# RevE-light.net
KiCad netlist of a schematic drawn in EAGLE
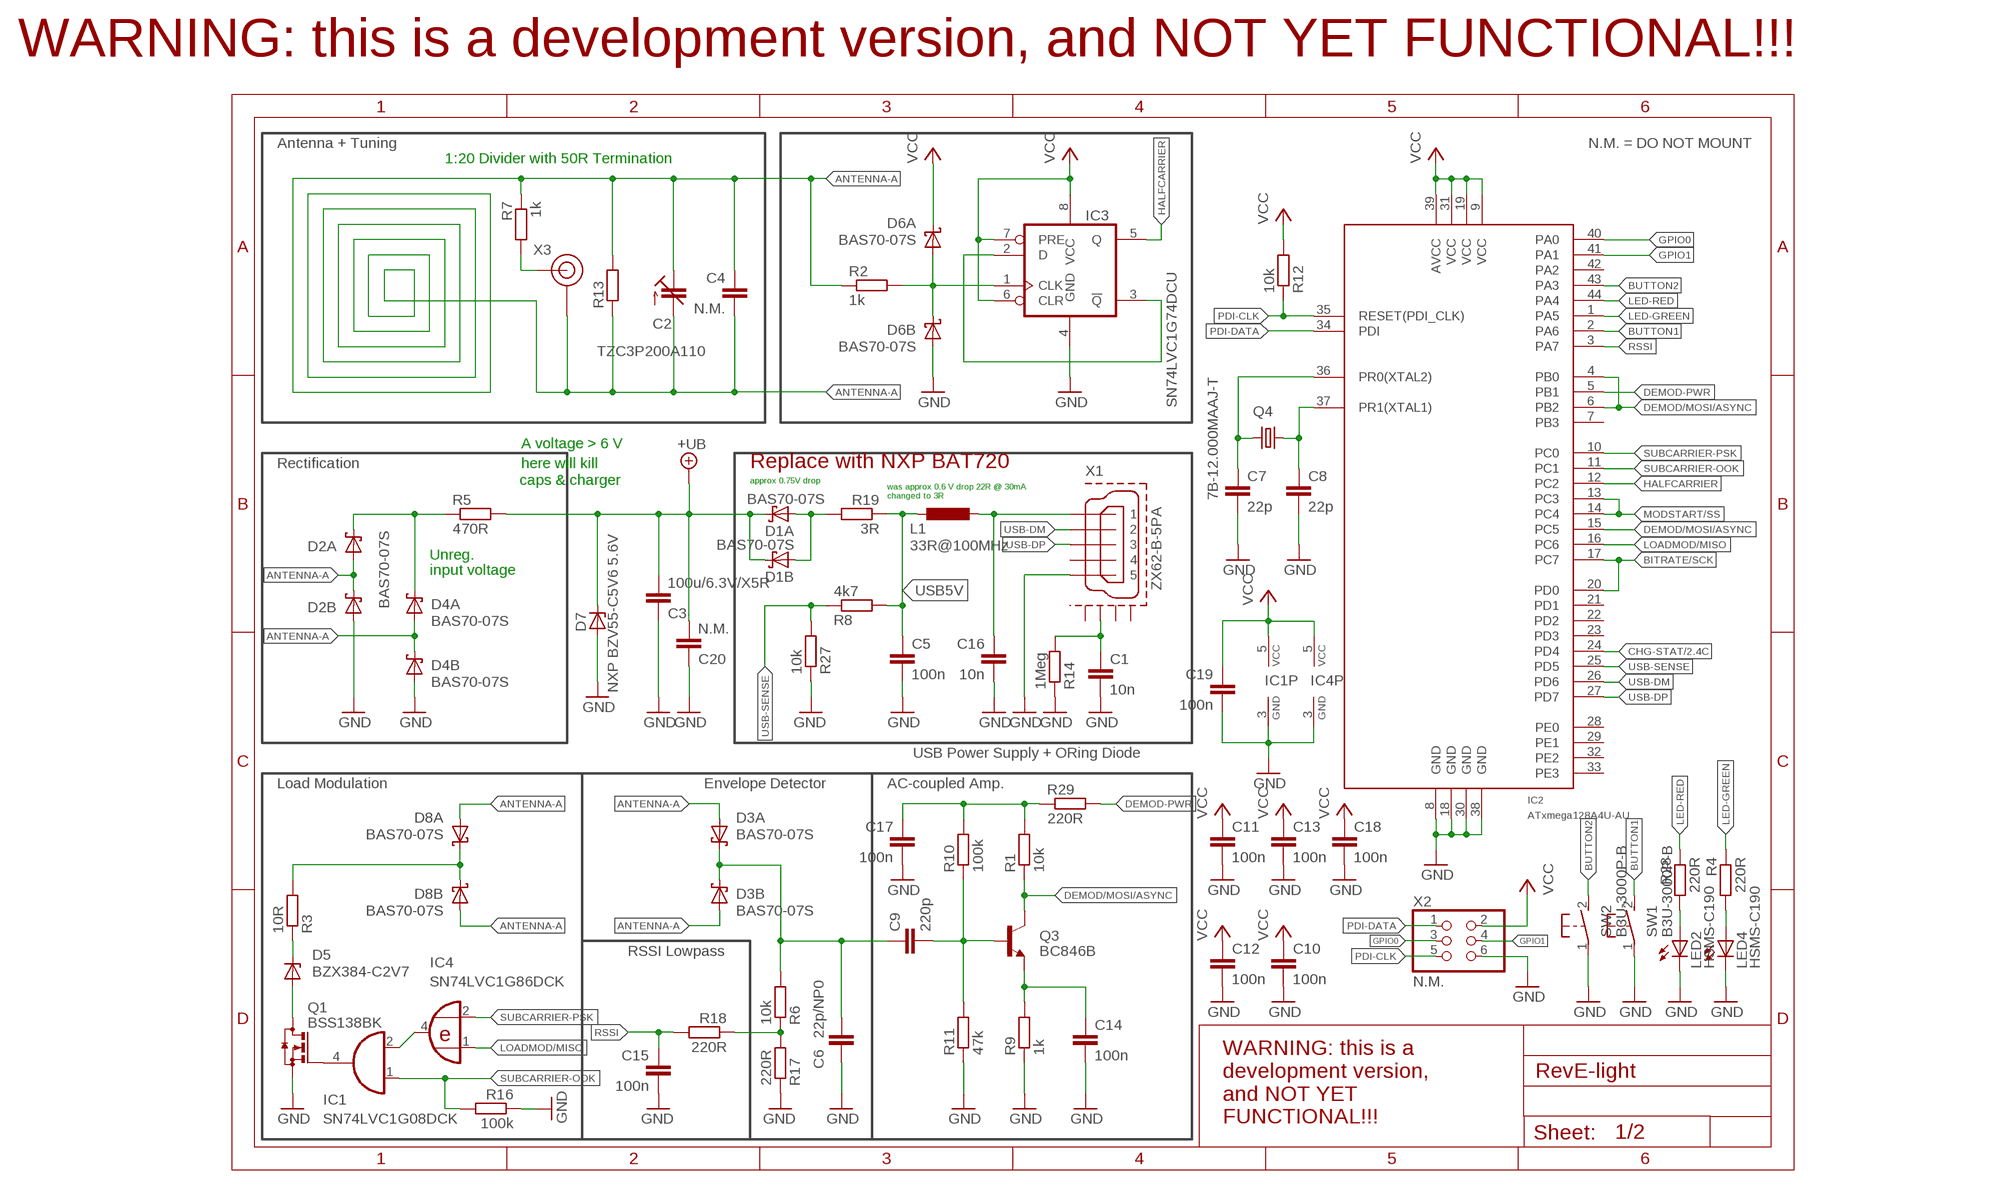
[diagram p0: schematic, sheet 1]
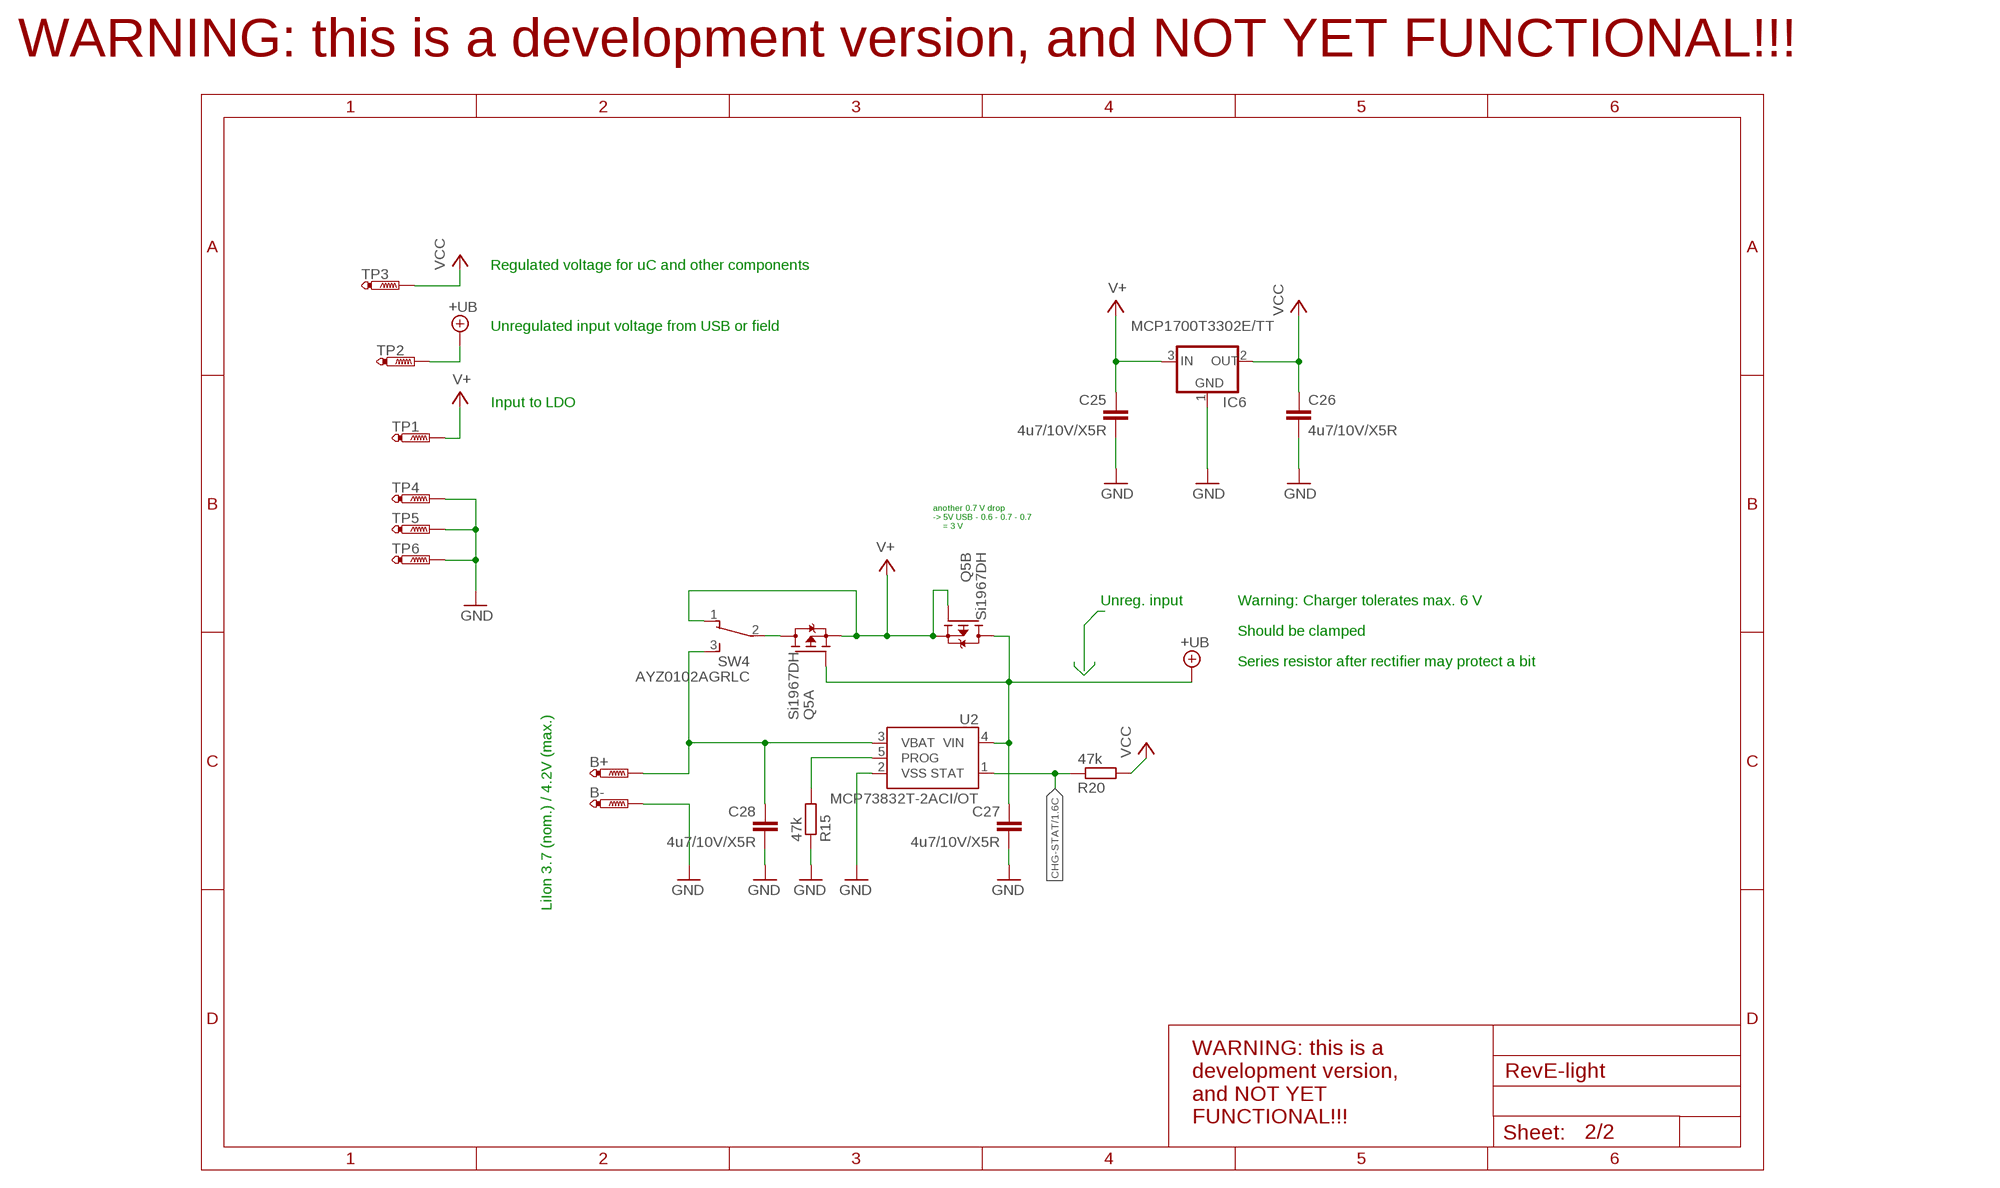
[diagram p1: schematic, sheet 2]

(export (version "E")
  (design (tool "Eeschema 10.0.6"))
  (components
    (comp (ref "C1")
      (value "10n")
      (footprint "eagle-import:C1206K")
      (libsource (lib "eagle-import") (part "C-EUC1206K"))
    )
    (comp (ref "C2")
      (value "TZC3P200A110")
      (footprint "eagle-import:TZC3P")
      (libsource (lib "eagle-import") (part "TZC3P"))
    )
    (comp (ref "C3")
      (value "100u/6.3V/X5R")
      (footprint "eagle-import:C1206K")
      (libsource (lib "eagle-import") (part "C-EUC1206K"))
    )
    (comp (ref "C4")
      (value "N.M.")
      (footprint "eagle-import:C1206")
      (libsource (lib "eagle-import") (part "C-EUC1206"))
    )
    (comp (ref "C5")
      (value "100n")
      (footprint "eagle-import:C1206K")
      (libsource (lib "eagle-import") (part "C-EUC1206K"))
    )
    (comp (ref "C6")
      (value "22p/NP0")
      (footprint "eagle-import:C0603K")
      (libsource (lib "eagle-import") (part "C-EUC0603K"))
    )
    (comp (ref "C7")
      (value "22p")
      (footprint "eagle-import:C0603K")
      (libsource (lib "eagle-import") (part "C-EUC0603K"))
    )
    (comp (ref "C8")
      (value "22p")
      (footprint "eagle-import:C0603K")
      (libsource (lib "eagle-import") (part "C-EUC0603K"))
    )
    (comp (ref "C9")
      (value "220p")
      (footprint "eagle-import:C0603K")
      (libsource (lib "eagle-import") (part "C-EUC0603K"))
    )
    (comp (ref "C10")
      (value "100n")
      (footprint "eagle-import:C0603K")
      (libsource (lib "eagle-import") (part "C-EUC0603K"))
    )
    (comp (ref "C11")
      (value "100n")
      (footprint "eagle-import:C0603K")
      (libsource (lib "eagle-import") (part "C-EUC0603K"))
    )
    (comp (ref "C12")
      (value "100n")
      (footprint "eagle-import:C0603K")
      (libsource (lib "eagle-import") (part "C-EUC0603K"))
    )
    (comp (ref "C13")
      (value "100n")
      (footprint "eagle-import:C0603K")
      (libsource (lib "eagle-import") (part "C-EUC0603K"))
    )
    (comp (ref "C14")
      (value "100n")
      (footprint "eagle-import:C0603K")
      (libsource (lib "eagle-import") (part "C-EUC0603K"))
    )
    (comp (ref "C15")
      (value "100n")
      (footprint "eagle-import:C0603K")
      (libsource (lib "eagle-import") (part "C-EUC0603K"))
    )
    (comp (ref "C16")
      (value "10n")
      (footprint "eagle-import:C1206K")
      (libsource (lib "eagle-import") (part "C-EUC1206K"))
    )
    (comp (ref "C17")
      (value "100n")
      (footprint "eagle-import:C0603K")
      (libsource (lib "eagle-import") (part "C-EUC0603K"))
    )
    (comp (ref "C18")
      (value "100n")
      (footprint "eagle-import:C0603K")
      (libsource (lib "eagle-import") (part "C-EUC0603K"))
    )
    (comp (ref "C19")
      (value "100n")
      (footprint "eagle-import:C0603K")
      (libsource (lib "eagle-import") (part "C-EUC0603K"))
    )
    (comp (ref "C20")
      (value "N.M.")
      (footprint "eagle-import:C1206K")
      (libsource (lib "eagle-import") (part "C-EUC1206K"))
    )
    (comp (ref "D1")
      (value "BAS70-07S")
      (footprint "eagle-import:SOT363_PHILIPS")
      (libsource (lib "eagle-import") (part "BAS70-07S"))
    )
    (comp (ref "D2")
      (value "BAS70-07S")
      (footprint "eagle-import:SOT363_PHILIPS")
      (libsource (lib "eagle-import") (part "BAS70-07S"))
    )
    (comp (ref "D3")
      (value "BAS70-07S")
      (footprint "eagle-import:SOT363_PHILIPS")
      (libsource (lib "eagle-import") (part "BAS70-07S"))
    )
    (comp (ref "D4")
      (value "BAS70-07S")
      (footprint "eagle-import:SOT363_PHILIPS")
      (libsource (lib "eagle-import") (part "BAS70-07S"))
    )
    (comp (ref "D5")
      (value "BZX384-C2V7")
      (footprint "eagle-import:SOD323")
      (libsource (lib "eagle-import") (part "BZX384"))
    )
    (comp (ref "D6")
      (value "BAS70-07S")
      (footprint "eagle-import:SOT363_PHILIPS")
      (libsource (lib "eagle-import") (part "BAS70-07S"))
    )
    (comp (ref "D7")
      (value "NXP BZV55-C5V6 5.6V")
      (footprint "eagle-import:SOD80C")
      (libsource (lib "eagle-import") (part "ZENER-DIODESOD80C"))
    )
    (comp (ref "D8")
      (value "BAS70-07S")
      (footprint "eagle-import:SOT363_PHILIPS")
      (libsource (lib "eagle-import") (part "BAS70-07S"))
    )
    (comp (ref "IC1")
      (value "SN74LVC1G08DCK")
      (footprint "eagle-import:SC70-5")
      (libsource (lib "eagle-import") (part "741G08DCKLVC"))
    )
    (comp (ref "IC2")
      (value "ATxmega128A4U-AU")
      (footprint "eagle-import:TQFP44")
      (libsource (lib "eagle-import") (part "ATXMEGA_A4-A"))
    )
    (comp (ref "IC3")
      (value "SN74LVC1G74DCU")
      (footprint "eagle-import:VSSOP8")
      (libsource (lib "eagle-import") (part "74LVC1G74DC"))
    )
    (comp (ref "IC4")
      (value "SN74LVC1G86DCK")
      (footprint "eagle-import:SC70-5")
      (libsource (lib "eagle-import") (part "741G86DCKAHC"))
    )
    (comp (ref "L1")
      (value "33R@100MHz")
      (footprint "eagle-import:L2012C")
      (libsource (lib "eagle-import") (part "L-EUL2012C"))
    )
    (comp (ref "LED2")
      (value "HSMS-C190")
      (footprint "eagle-import:CHIPLED_0603")
      (libsource (lib "eagle-import") (part "LEDCHIPLED_0603"))
    )
    (comp (ref "LED4")
      (value "HSMS-C190")
      (footprint "eagle-import:CHIPLED_0603")
      (libsource (lib "eagle-import") (part "LEDCHIPLED_0603"))
    )
    (comp (ref "Q1")
      (value "BSS138BK")
      (footprint "eagle-import:SOT23")
      (libsource (lib "eagle-import") (part "BSS123"))
    )
    (comp (ref "Q3")
      (value "BC846B")
      (footprint "eagle-import:SOT23")
      (libsource (lib "eagle-import") (part "BC846SMDB"))
    )
    (comp (ref "Q4")
      (value "7B-12.000MAAJ-T")
      (footprint "eagle-import:5MMX3.2MM")
      (libsource (lib "eagle-import") (part "TXC7B"))
    )
    (comp (ref "R1")
      (value "10k")
      (footprint "eagle-import:R0603")
      (libsource (lib "eagle-import") (part "R-EU_R0603"))
    )
    (comp (ref "R2")
      (value "1k")
      (footprint "eagle-import:R0603")
      (libsource (lib "eagle-import") (part "R-EU_R0603"))
    )
    (comp (ref "R3")
      (value "10R")
      (footprint "eagle-import:R0603")
      (libsource (lib "eagle-import") (part "R-EU_R0603"))
    )
    (comp (ref "R4")
      (value "220R")
      (footprint "eagle-import:R0603")
      (libsource (lib "eagle-import") (part "R-EU_R0603"))
    )
    (comp (ref "R5")
      (value "470R")
      (footprint "eagle-import:R1206")
      (libsource (lib "eagle-import") (part "R-EU_R1206"))
    )
    (comp (ref "R6")
      (value "10k")
      (footprint "eagle-import:R0603")
      (libsource (lib "eagle-import") (part "R-EU_R0603"))
    )
    (comp (ref "R7")
      (value "1k")
      (footprint "eagle-import:R1206")
      (libsource (lib "eagle-import") (part "R-EU_R1206"))
    )
    (comp (ref "R8")
      (value "4k7")
      (footprint "eagle-import:R0603")
      (libsource (lib "eagle-import") (part "R-EU_R0603"))
    )
    (comp (ref "R9")
      (value "1k")
      (footprint "eagle-import:R0603")
      (libsource (lib "eagle-import") (part "R-EU_R0603"))
    )
    (comp (ref "R10")
      (value "100k")
      (footprint "eagle-import:R0603")
      (libsource (lib "eagle-import") (part "R-EU_R0603"))
    )
    (comp (ref "R11")
      (value "47k")
      (footprint "eagle-import:R0603")
      (libsource (lib "eagle-import") (part "R-EU_R0603"))
    )
    (comp (ref "R12")
      (value "10k")
      (footprint "eagle-import:R0603")
      (libsource (lib "eagle-import") (part "R-EU_R0603"))
    )
    (comp (ref "R13")
      (value "R-EU_M1206")
      (footprint "eagle-import:M1206")
      (libsource (lib "eagle-import") (part "R-EU_M1206"))
    )
    (comp (ref "R14")
      (value "1Meg")
      (footprint "eagle-import:M0805")
      (libsource (lib "eagle-import") (part "R-EU_M0805"))
    )
    (comp (ref "R16")
      (value "100k")
      (footprint "eagle-import:R0603")
      (libsource (lib "eagle-import") (part "R-EU_R0603"))
    )
    (comp (ref "R17")
      (value "220R")
      (footprint "eagle-import:R0603")
      (libsource (lib "eagle-import") (part "R-EU_R0603"))
    )
    (comp (ref "R18")
      (value "220R")
      (footprint "eagle-import:R0603")
      (libsource (lib "eagle-import") (part "R-EU_R0603"))
    )
    (comp (ref "R19")
      (value "3R")
      (footprint "eagle-import:M0805")
      (libsource (lib "eagle-import") (part "R-EU_M0805"))
    )
    (comp (ref "R27")
      (value "10k")
      (footprint "eagle-import:R0603")
      (libsource (lib "eagle-import") (part "R-EU_R0603"))
    )
    (comp (ref "R28")
      (value "220R")
      (footprint "eagle-import:R0603")
      (libsource (lib "eagle-import") (part "R-EU_R0603"))
    )
    (comp (ref "R29")
      (value "220R")
      (footprint "eagle-import:R0603")
      (libsource (lib "eagle-import") (part "R-EU_R0603"))
    )
    (comp (ref "SW1")
      (value "B3U-3000P-B")
      (footprint "eagle-import:B3U-3000P-B")
      (libsource (lib "eagle-import") (part "B3U-3000P-B"))
    )
    (comp (ref "SW2")
      (value "B3U-3000P-B")
      (footprint "eagle-import:B3U-3000P-B")
      (libsource (lib "eagle-import") (part "B3U-3000P-B"))
    )
    (comp (ref "X1")
      (value "ZX62-B-5PA")
      (footprint "eagle-import:ZX62-B-5PA-LONG")
      (libsource (lib "eagle-import") (part "ZX62-B-5PA-LONG"))
    )
    (comp (ref "X2")
      (value "N.M.")
      (footprint "eagle-import:PINHD-2X3-2.54-EDGE")
      (libsource (lib "eagle-import") (part "PINHD-2X3-2.54-EDGE"))
    )
    (comp (ref "X3")
      (value "U.FL-R-SMT")
      (footprint "eagle-import:U.FL-R-SMT")
      (libsource (lib "eagle-import") (part "U.FL-R-SMT"))
    )
    (comp (ref "B+")
      (value "PTR1TP18SQ")
      (footprint "eagle-import:TP18SQ")
      (libsource (lib "eagle-import") (part "PTR1TP18SQ"))
    )
    (comp (ref "B-")
      (value "PTR1TP18SQ")
      (footprint "eagle-import:TP18SQ")
      (libsource (lib "eagle-import") (part "PTR1TP18SQ"))
    )
    (comp (ref "C25")
      (value "4u7/10V/X5R")
      (footprint "eagle-import:C0603K")
      (libsource (lib "eagle-import") (part "C-EUC0603K"))
    )
    (comp (ref "C26")
      (value "4u7/10V/X5R")
      (footprint "eagle-import:C0603K")
      (libsource (lib "eagle-import") (part "C-EUC0603K"))
    )
    (comp (ref "C27")
      (value "4u7/10V/X5R")
      (footprint "eagle-import:C0603K")
      (libsource (lib "eagle-import") (part "C-EUC0603K"))
    )
    (comp (ref "C28")
      (value "4u7/10V/X5R")
      (footprint "eagle-import:C0603K")
      (libsource (lib "eagle-import") (part "C-EUC0603K"))
    )
    (comp (ref "IC6")
      (value "MCP1700T3302E/TT")
      (footprint "eagle-import:SOT23")
      (libsource (lib "eagle-import") (part "MCP1702"))
    )
    (comp (ref "Q5")
      (value "Si1967DH")
      (footprint "eagle-import:SOT363")
      (libsource (lib "eagle-import") (part "BSS84AKS"))
    )
    (comp (ref "R15")
      (value "47k")
      (footprint "eagle-import:R0603")
      (libsource (lib "eagle-import") (part "R-EU_R0603"))
    )
    (comp (ref "R20")
      (value "47k")
      (footprint "eagle-import:R0603")
      (libsource (lib "eagle-import") (part "R-EU_R0603"))
    )
    (comp (ref "SW4")
      (value "AYZ0102AGRLC")
      (footprint "eagle-import:AYZ0102AGRLC")
      (libsource (lib "eagle-import") (part "AYZ0102AGRLC"))
    )
    (comp (ref "TP1")
      (value "PTR1TP07R")
      (footprint "eagle-import:TP07R")
      (libsource (lib "eagle-import") (part "PTR1TP07R"))
    )
    (comp (ref "TP2")
      (value "PTR1TP07R")
      (footprint "eagle-import:TP07R")
      (libsource (lib "eagle-import") (part "PTR1TP07R"))
    )
    (comp (ref "TP3")
      (value "PTR1TP07R")
      (footprint "eagle-import:TP07R")
      (libsource (lib "eagle-import") (part "PTR1TP07R"))
    )
    (comp (ref "TP4")
      (value "PTR1TP07R")
      (footprint "eagle-import:TP07R")
      (libsource (lib "eagle-import") (part "PTR1TP07R"))
    )
    (comp (ref "TP5")
      (value "PTR1TP07R")
      (footprint "eagle-import:TP07R")
      (libsource (lib "eagle-import") (part "PTR1TP07R"))
    )
    (comp (ref "TP6")
      (value "PTR1TP07R")
      (footprint "eagle-import:TP07R")
      (libsource (lib "eagle-import") (part "PTR1TP07R"))
    )
    (comp (ref "U2")
      (value "MCP73832T-2ACI/OT")
      (footprint "eagle-import:SOT23-5")
      (libsource (lib "eagle-import") (part "MCP73831"))
    )
  )
  (nets
    (net (code "1") (name "+UB") (class "Default")
      (node (ref "C20") (pin "2") (pinfunction "2_2") (pintype "passive"))
      (node (ref "C27") (pin "1") (pinfunction "1_1") (pintype "passive"))
      (node (ref "C3") (pin "2") (pinfunction "2_2") (pintype "passive"))
      (node (ref "D1") (pin "3") (pinfunction "C_3") (pintype "passive"))
      (node (ref "D1") (pin "6") (pinfunction "C_6") (pintype "passive"))
      (node (ref "D7") (pin "C") (pinfunction "C_C") (pintype "passive"))
      (node (ref "Q5") (pin "2") (pinfunction "G_2") (pintype "passive"))
      (node (ref "Q5") (pin "3") (pinfunction "D_3") (pintype "passive"))
      (node (ref "R5") (pin "2") (pinfunction "2_2") (pintype "passive"))
      (node (ref "TP2") (pin "TP") (pinfunction "TP_TP") (pintype "input"))
      (node (ref "U2") (pin "4") (pinfunction "VIN_4") (pintype "power_in"))
    )
    (net (code "2") (name "ANTENNA-A") (class "Default")
      (node (ref "C2") (pin "1") (pinfunction "A_1") (pintype "passive"))
      (node (ref "C2") (pin "2") (pinfunction "E_2") (pintype "passive"))
      (node (ref "C4") (pin "1") (pinfunction "1_1") (pintype "passive"))
      (node (ref "C4") (pin "2") (pinfunction "2_2") (pintype "passive"))
      (node (ref "D2") (pin "1") (pinfunction "A_1") (pintype "passive"))
      (node (ref "D2") (pin "3") (pinfunction "C_3") (pintype "passive"))
      (node (ref "D3") (pin "1") (pinfunction "A_1") (pintype "passive"))
      (node (ref "D3") (pin "4") (pinfunction "A_4") (pintype "passive"))
      (node (ref "D4") (pin "1") (pinfunction "A_1") (pintype "passive"))
      (node (ref "D4") (pin "3") (pinfunction "C_3") (pintype "passive"))
      (node (ref "D8") (pin "1") (pinfunction "A_1") (pintype "passive"))
      (node (ref "D8") (pin "4") (pinfunction "A_4") (pintype "passive"))
      (node (ref "R13") (pin "1") (pinfunction "1_1") (pintype "passive"))
      (node (ref "R13") (pin "2") (pinfunction "2_2") (pintype "passive"))
      (node (ref "R2") (pin "1") (pinfunction "1_1") (pintype "passive"))
      (node (ref "R7") (pin "1") (pinfunction "1_1") (pintype "passive"))
      (node (ref "X3") (pin "GND2") (pinfunction "GND_GND2") (pintype "bidirectional"))
    )
    (net (code "3") (name "BITRATE{slash}SCK") (class "Default")
      (node (ref "IC2") (pin "17") (pinfunction "PC7_17") (pintype "bidirectional"))
      (node (ref "IC2") (pin "20") (pinfunction "PD0_20") (pintype "bidirectional"))
    )
    (net (code "4") (name "BUTTON1") (class "Default")
      (node (ref "IC2") (pin "2") (pinfunction "PA6_2") (pintype "bidirectional"))
      (node (ref "SW1") (pin "2") (pinfunction "S_2") (pintype "passive"))
    )
    (net (code "5") (name "BUTTON2") (class "Default")
      (node (ref "IC2") (pin "43") (pinfunction "PA3_43") (pintype "bidirectional"))
      (node (ref "SW2") (pin "2") (pinfunction "S_2") (pintype "passive"))
    )
    (net (code "6") (name "CHG-STAT") (class "Default")
      (node (ref "IC2") (pin "24") (pinfunction "PD4_24") (pintype "bidirectional"))
      (node (ref "R20") (pin "1") (pinfunction "1_1") (pintype "passive"))
      (node (ref "U2") (pin "1") (pinfunction "STAT_1") (pintype "output"))
    )
    (net (code "7") (name "DEMOD-PWR") (class "Default")
      (node (ref "IC2") (pin "5") (pinfunction "PB1_5") (pintype "bidirectional"))
      (node (ref "R29") (pin "2") (pinfunction "2_2") (pintype "passive"))
    )
    (net (code "8") (name "DEMOD{slash}MOSI{slash}ASYNC") (class "Default")
      (node (ref "IC2") (pin "15") (pinfunction "PC5_15") (pintype "bidirectional"))
      (node (ref "IC2") (pin "4") (pinfunction "PB0_4") (pintype "bidirectional"))
      (node (ref "IC2") (pin "6") (pinfunction "PB2_6") (pintype "bidirectional"))
      (node (ref "Q3") (pin "3") (pinfunction "C_3") (pintype "passive"))
      (node (ref "R1") (pin "1") (pinfunction "1_1") (pintype "passive"))
    )
    (net (code "9") (name "GND") (class "Default")
      (node (ref "B-") (pin "TP") (pinfunction "TP_TP") (pintype "input"))
      (node (ref "C1") (pin "2") (pinfunction "2_2") (pintype "passive"))
      (node (ref "C10") (pin "2") (pinfunction "2_2") (pintype "passive"))
      (node (ref "C11") (pin "2") (pinfunction "2_2") (pintype "passive"))
      (node (ref "C12") (pin "2") (pinfunction "2_2") (pintype "passive"))
      (node (ref "C13") (pin "2") (pinfunction "2_2") (pintype "passive"))
      (node (ref "C14") (pin "2") (pinfunction "2_2") (pintype "passive"))
      (node (ref "C15") (pin "2") (pinfunction "2_2") (pintype "passive"))
      (node (ref "C16") (pin "2") (pinfunction "2_2") (pintype "passive"))
      (node (ref "C17") (pin "2") (pinfunction "2_2") (pintype "passive"))
      (node (ref "C18") (pin "2") (pinfunction "2_2") (pintype "passive"))
      (node (ref "C19") (pin "2") (pinfunction "2_2") (pintype "passive"))
      (node (ref "C20") (pin "1") (pinfunction "1_1") (pintype "passive"))
      (node (ref "C25") (pin "2") (pinfunction "2_2") (pintype "passive"))
      (node (ref "C26") (pin "2") (pinfunction "2_2") (pintype "passive"))
      (node (ref "C27") (pin "2") (pinfunction "2_2") (pintype "passive"))
      (node (ref "C28") (pin "2") (pinfunction "2_2") (pintype "passive"))
      (node (ref "C3") (pin "1") (pinfunction "1_1") (pintype "passive"))
      (node (ref "C5") (pin "2") (pinfunction "2_2") (pintype "passive"))
      (node (ref "C6") (pin "2") (pinfunction "2_2") (pintype "passive"))
      (node (ref "C7") (pin "2") (pinfunction "2_2") (pintype "passive"))
      (node (ref "C8") (pin "2") (pinfunction "2_2") (pintype "passive"))
      (node (ref "D2") (pin "4") (pinfunction "A_4") (pintype "passive"))
      (node (ref "D4") (pin "4") (pinfunction "A_4") (pintype "passive"))
      (node (ref "D6") (pin "4") (pinfunction "A_4") (pintype "passive"))
      (node (ref "D7") (pin "A") (pinfunction "A_A") (pintype "passive"))
      (node (ref "IC1") (pin "3") (pinfunction "GND_3") (pintype "power_in"))
      (node (ref "IC2") (pin "18") (pinfunction "GND_18") (pintype "bidirectional"))
      (node (ref "IC2") (pin "30") (pinfunction "GND_30") (pintype "bidirectional"))
      (node (ref "IC2") (pin "38") (pinfunction "GND_38") (pintype "bidirectional"))
      (node (ref "IC2") (pin "8") (pinfunction "GND_8") (pintype "bidirectional"))
      (node (ref "IC3") (pin "4") (pinfunction "GND_4") (pintype "bidirectional"))
      (node (ref "IC4") (pin "3") (pinfunction "GND_3") (pintype "power_in"))
      (node (ref "IC6") (pin "1") (pinfunction "GND_1") (pintype "input"))
      (node (ref "LED2") (pin "C") (pinfunction "C_C") (pintype "passive"))
      (node (ref "LED4") (pin "C") (pinfunction "C_C") (pintype "passive"))
      (node (ref "Q1") (pin "2") (pinfunction "S_2") (pintype "passive"))
      (node (ref "R11") (pin "1") (pinfunction "1_1") (pintype "passive"))
      (node (ref "R14") (pin "1") (pinfunction "1_1") (pintype "passive"))
      (node (ref "R15") (pin "1") (pinfunction "1_1") (pintype "passive"))
      (node (ref "R16") (pin "1") (pinfunction "1_1") (pintype "passive"))
      (node (ref "R17") (pin "1") (pinfunction "1_1") (pintype "passive"))
      (node (ref "R27") (pin "1") (pinfunction "1_1") (pintype "passive"))
      (node (ref "R9") (pin "1") (pinfunction "1_1") (pintype "passive"))
      (node (ref "SW1") (pin "1") (pinfunction "P_1") (pintype "passive"))
      (node (ref "SW2") (pin "1") (pinfunction "P_1") (pintype "passive"))
      (node (ref "TP4") (pin "TP") (pinfunction "TP_TP") (pintype "input"))
      (node (ref "TP5") (pin "TP") (pinfunction "TP_TP") (pintype "input"))
      (node (ref "TP6") (pin "TP") (pinfunction "TP_TP") (pintype "input"))
      (node (ref "U2") (pin "2") (pinfunction "VSS_2") (pintype "power_in"))
      (node (ref "X1") (pin "5") (pinfunction "5_5") (pintype "input"))
      (node (ref "X2") (pin "6") (pinfunction "6_6") (pintype "passive"))
    )
    (net (code "10") (name "GPIO0") (class "Default")
      (node (ref "IC2") (pin "40") (pinfunction "PA0_40") (pintype "bidirectional"))
      (node (ref "X2") (pin "3") (pinfunction "3_3") (pintype "passive"))
    )
    (net (code "11") (name "GPIO1") (class "Default")
      (node (ref "IC2") (pin "41") (pinfunction "PA1_41") (pintype "bidirectional"))
      (node (ref "X2") (pin "4") (pinfunction "4_4") (pintype "passive"))
    )
    (net (code "12") (name "HALFCARRIER") (class "Default")
      (node (ref "IC2") (pin "12") (pinfunction "PC2_12") (pintype "bidirectional"))
      (node (ref "IC3") (pin "5") (pinfunction "Q_5") (pintype "output"))
    )
    (net (code "13") (name "LED-GREEN") (class "Default")
      (node (ref "IC2") (pin "1") (pinfunction "PA5_1") (pintype "bidirectional"))
      (node (ref "R4") (pin "1") (pinfunction "1_1") (pintype "passive"))
    )
    (net (code "14") (name "LED-RED") (class "Default")
      (node (ref "IC2") (pin "44") (pinfunction "PA4_44") (pintype "bidirectional"))
      (node (ref "R28") (pin "1") (pinfunction "1_1") (pintype "passive"))
    )
    (net (code "15") (name "LOADMOD{slash}MISO") (class "Default")
      (node (ref "IC2") (pin "16") (pinfunction "PC6_16") (pintype "bidirectional"))
      (node (ref "IC4") (pin "1") (pinfunction "I0_1") (pintype "input"))
    )
    (net (code "16") (name "MODSTART{slash}SS") (class "Default")
      (node (ref "IC2") (pin "13") (pinfunction "PC3_13") (pintype "bidirectional"))
      (node (ref "IC2") (pin "14") (pinfunction "PC4_14") (pintype "bidirectional"))
    )
    (net (code "17") (name "Net-(C16-Pad1)") (class "Default")
      (node (ref "C16") (pin "1") (pinfunction "1_1") (pintype "passive"))
      (node (ref "L1") (pin "1") (pinfunction "1_1") (pintype "passive"))
      (node (ref "X1") (pin "1") (pinfunction "1_1") (pintype "input"))
    )
    (net (code "18") (name "Net-(C17-Pad1)") (class "Default")
      (node (ref "C17") (pin "1") (pinfunction "1_1") (pintype "passive"))
      (node (ref "R1") (pin "2") (pinfunction "2_2") (pintype "passive"))
      (node (ref "R10") (pin "2") (pinfunction "2_2") (pintype "passive"))
      (node (ref "R29") (pin "1") (pinfunction "1_1") (pintype "passive"))
    )
    (net (code "19") (name "Net-(D1A-A)") (class "Default")
      (node (ref "D1") (pin "1") (pinfunction "A_1") (pintype "passive"))
      (node (ref "D1") (pin "4") (pinfunction "A_4") (pintype "passive"))
      (node (ref "R19") (pin "2") (pinfunction "2_2") (pintype "passive"))
    )
    (net (code "20") (name "Net-(D2A-C)") (class "Default")
      (node (ref "D2") (pin "6") (pinfunction "C_6") (pintype "passive"))
      (node (ref "D4") (pin "6") (pinfunction "C_6") (pintype "passive"))
      (node (ref "R5") (pin "1") (pinfunction "1_1") (pintype "passive"))
    )
    (net (code "21") (name "Net-(D3A-C)") (class "Default")
      (node (ref "C6") (pin "1") (pinfunction "1_1") (pintype "passive"))
      (node (ref "C9") (pin "1") (pinfunction "1_1") (pintype "passive"))
      (node (ref "D3") (pin "3") (pinfunction "C_3") (pintype "passive"))
      (node (ref "D3") (pin "6") (pinfunction "C_6") (pintype "passive"))
      (node (ref "R6") (pin "2") (pinfunction "2_2") (pintype "passive"))
    )
    (net (code "22") (name "Net-(D5-A)") (class "Default")
      (node (ref "D5") (pin "2") (pinfunction "A_2") (pintype "passive"))
      (node (ref "Q1") (pin "3") (pinfunction "D_3") (pintype "passive"))
    )
    (net (code "23") (name "Net-(D5-C)") (class "Default")
      (node (ref "D5") (pin "1") (pinfunction "C_1") (pintype "passive"))
      (node (ref "R3") (pin "1") (pinfunction "1_1") (pintype "passive"))
    )
    (net (code "24") (name "Net-(D6A-A)") (class "Default")
      (node (ref "D6") (pin "1") (pinfunction "A_1") (pintype "passive"))
      (node (ref "D6") (pin "3") (pinfunction "C_3") (pintype "passive"))
      (node (ref "IC3") (pin "1") (pinfunction "CLK_1") (pintype "input"))
      (node (ref "R2") (pin "2") (pinfunction "2_2") (pintype "passive"))
    )
    (net (code "25") (name "Net-(D8A-C)") (class "Default")
      (node (ref "D8") (pin "3") (pinfunction "C_3") (pintype "passive"))
      (node (ref "D8") (pin "6") (pinfunction "C_6") (pintype "passive"))
      (node (ref "R3") (pin "2") (pinfunction "2_2") (pintype "passive"))
    )
    (net (code "26") (name "Net-(IC1A-I1)") (class "Default")
      (node (ref "IC1") (pin "2") (pinfunction "I1_2") (pintype "input"))
      (node (ref "IC4") (pin "4") (pinfunction "O_4") (pintype "output"))
    )
    (net (code "27") (name "Net-(IC1A-O)") (class "Default")
      (node (ref "IC1") (pin "4") (pinfunction "O_4") (pintype "output"))
      (node (ref "Q1") (pin "1") (pinfunction "G_1") (pintype "passive"))
    )
    (net (code "28") (name "Net-(IC2-PR0(XTAL2))") (class "Default")
      (node (ref "C7") (pin "1") (pinfunction "1_1") (pintype "passive"))
      (node (ref "IC2") (pin "36") (pinfunction "PR0(XTAL2)_36") (pintype "bidirectional"))
      (node (ref "Q4") (pin "3") (pinfunction "2_3") (pintype "passive"))
    )
    (net (code "29") (name "Net-(IC2-PR1(XTAL1))") (class "Default")
      (node (ref "C8") (pin "1") (pinfunction "1_1") (pintype "passive"))
      (node (ref "IC2") (pin "37") (pinfunction "PR1(XTAL1)_37") (pintype "bidirectional"))
      (node (ref "Q4") (pin "1") (pinfunction "1_1") (pintype "passive"))
    )
    (net (code "30") (name "Net-(IC3-D)") (class "Default")
      (node (ref "IC3") (pin "2") (pinfunction "D_2") (pintype "input"))
      (node (ref "IC3") (pin "3") (pinfunction "~{Q}_3") (pintype "output"))
    )
    (net (code "31") (name "Net-(LED2-PadA)") (class "Default")
      (node (ref "LED2") (pin "A") (pinfunction "A_A") (pintype "passive"))
      (node (ref "R28") (pin "2") (pinfunction "2_2") (pintype "passive"))
    )
    (net (code "32") (name "Net-(LED4-PadA)") (class "Default")
      (node (ref "LED4") (pin "A") (pinfunction "A_A") (pintype "passive"))
      (node (ref "R4") (pin "2") (pinfunction "2_2") (pintype "passive"))
    )
    (net (code "33") (name "Net-(Q3-B)") (class "Default")
      (node (ref "C9") (pin "2") (pinfunction "2_2") (pintype "passive"))
      (node (ref "Q3") (pin "1") (pinfunction "B_1") (pintype "passive"))
      (node (ref "R10") (pin "1") (pinfunction "1_1") (pintype "passive"))
      (node (ref "R11") (pin "2") (pinfunction "2_2") (pintype "passive"))
    )
    (net (code "34") (name "Net-(Q3-E)") (class "Default")
      (node (ref "C14") (pin "1") (pinfunction "1_1") (pintype "passive"))
      (node (ref "Q3") (pin "2") (pinfunction "E_2") (pintype "passive"))
      (node (ref "R9") (pin "2") (pinfunction "2_2") (pintype "passive"))
    )
    (net (code "35") (name "Net-(Q5A-D)") (class "Default")
      (node (ref "Q5") (pin "6") (pinfunction "D_6") (pintype "passive"))
      (node (ref "SW4") (pin "2") (pinfunction "P_2") (pintype "passive"))
    )
    (net (code "36") (name "Net-(R7-Pad2)") (class "Default")
      (node (ref "R7") (pin "2") (pinfunction "2_2") (pintype "passive"))
      (node (ref "X3") (pin "SIG") (pinfunction "SIG_SIG") (pintype "bidirectional"))
    )
    (net (code "37") (name "Net-(R17-Pad2)") (class "Default")
      (node (ref "R17") (pin "2") (pinfunction "2_2") (pintype "passive"))
      (node (ref "R18") (pin "1") (pinfunction "1_1") (pintype "passive"))
      (node (ref "R6") (pin "1") (pinfunction "1_1") (pintype "passive"))
    )
    (net (code "38") (name "Net-(SW4-S)") (class "Default")
      (node (ref "B+") (pin "TP") (pinfunction "TP_TP") (pintype "input"))
      (node (ref "C28") (pin "1") (pinfunction "1_1") (pintype "passive"))
      (node (ref "SW4") (pin "3") (pinfunction "S_3") (pintype "passive"))
      (node (ref "U2") (pin "3") (pinfunction "VBAT_3") (pintype "power_in"))
    )
    (net (code "39") (name "Net-(U2-PROG)") (class "Default")
      (node (ref "R15") (pin "2") (pinfunction "2_2") (pintype "passive"))
      (node (ref "U2") (pin "5") (pinfunction "PROG_5") (pintype "input"))
    )
    (net (code "40") (name "Net-(X1-GND2)") (class "Default")
      (node (ref "C1") (pin "1") (pinfunction "1_1") (pintype "passive"))
      (node (ref "R14") (pin "2") (pinfunction "2_2") (pintype "passive"))
      (node (ref "X1") (pin "P$2") (pinfunction "GND2_P$2") (pintype "bidirectional"))
    )
    (net (code "41") (name "PDI-CLK") (class "Default")
      (node (ref "IC2") (pin "35") (pinfunction "RESET(PDI_CLK)_35") (pintype "bidirectional"))
      (node (ref "R12") (pin "1") (pinfunction "1_1") (pintype "passive"))
      (node (ref "X2") (pin "5") (pinfunction "5_5") (pintype "passive"))
    )
    (net (code "42") (name "PDI-DATA") (class "Default")
      (node (ref "IC2") (pin "34") (pinfunction "PDI_34") (pintype "bidirectional"))
      (node (ref "X2") (pin "1") (pinfunction "1_1") (pintype "passive"))
    )
    (net (code "43") (name "RSSI") (class "Default")
      (node (ref "C15") (pin "1") (pinfunction "1_1") (pintype "passive"))
      (node (ref "IC2") (pin "3") (pinfunction "PA7_3") (pintype "bidirectional"))
      (node (ref "R18") (pin "2") (pinfunction "2_2") (pintype "passive"))
    )
    (net (code "44") (name "SUBCARRIER-OOK") (class "Default")
      (node (ref "IC1") (pin "1") (pinfunction "I0_1") (pintype "input"))
      (node (ref "IC2") (pin "11") (pinfunction "PC1_11") (pintype "bidirectional"))
      (node (ref "R16") (pin "2") (pinfunction "2_2") (pintype "passive"))
    )
    (net (code "45") (name "SUBCARRIER-PSK") (class "Default")
      (node (ref "IC2") (pin "10") (pinfunction "PC0_10") (pintype "bidirectional"))
      (node (ref "IC4") (pin "2") (pinfunction "I1_2") (pintype "input"))
    )
    (net (code "46") (name "USB-DM") (class "Default")
      (node (ref "IC2") (pin "26") (pinfunction "PD6_26") (pintype "bidirectional"))
      (node (ref "X1") (pin "2") (pinfunction "2_2") (pintype "input"))
    )
    (net (code "47") (name "USB-DP") (class "Default")
      (node (ref "IC2") (pin "27") (pinfunction "PD7_27") (pintype "bidirectional"))
      (node (ref "X1") (pin "3") (pinfunction "3_3") (pintype "input"))
    )
    (net (code "48") (name "USB-SENSE") (class "Default")
      (node (ref "IC2") (pin "25") (pinfunction "PD5_25") (pintype "bidirectional"))
      (node (ref "R27") (pin "2") (pinfunction "2_2") (pintype "passive"))
      (node (ref "R8") (pin "1") (pinfunction "1_1") (pintype "passive"))
    )
    (net (code "49") (name "USB5V") (class "Default")
      (node (ref "C5") (pin "1") (pinfunction "1_1") (pintype "passive"))
      (node (ref "L1") (pin "2") (pinfunction "2_2") (pintype "passive"))
      (node (ref "R19") (pin "1") (pinfunction "1_1") (pintype "passive"))
      (node (ref "R8") (pin "2") (pinfunction "2_2") (pintype "passive"))
    )
    (net (code "50") (name "V+") (class "Default")
      (node (ref "C25") (pin "1") (pinfunction "1_1") (pintype "passive"))
      (node (ref "IC6") (pin "3") (pinfunction "IN_3") (pintype "input"))
      (node (ref "Q5") (pin "1") (pinfunction "S_1") (pintype "passive"))
      (node (ref "Q5") (pin "4") (pinfunction "S_4") (pintype "passive"))
      (node (ref "Q5") (pin "5") (pinfunction "G_5") (pintype "passive"))
      (node (ref "SW4") (pin "1") (pinfunction "O_1") (pintype "passive"))
      (node (ref "TP1") (pin "TP") (pinfunction "TP_TP") (pintype "input"))
    )
    (net (code "51") (name "VCC") (class "Default")
      (node (ref "C10") (pin "1") (pinfunction "1_1") (pintype "passive"))
      (node (ref "C11") (pin "1") (pinfunction "1_1") (pintype "passive"))
      (node (ref "C12") (pin "1") (pinfunction "1_1") (pintype "passive"))
      (node (ref "C13") (pin "1") (pinfunction "1_1") (pintype "passive"))
      (node (ref "C18") (pin "1") (pinfunction "1_1") (pintype "passive"))
      (node (ref "C19") (pin "1") (pinfunction "1_1") (pintype "passive"))
      (node (ref "C26") (pin "1") (pinfunction "1_1") (pintype "passive"))
      (node (ref "D6") (pin "6") (pinfunction "C_6") (pintype "passive"))
      (node (ref "IC1") (pin "5") (pinfunction "VCC_5") (pintype "power_in"))
      (node (ref "IC2") (pin "19") (pinfunction "VCC_19") (pintype "bidirectional"))
      (node (ref "IC2") (pin "31") (pinfunction "VCC_31") (pintype "bidirectional"))
      (node (ref "IC2") (pin "39") (pinfunction "AVCC_39") (pintype "bidirectional"))
      (node (ref "IC2") (pin "9") (pinfunction "VCC_9") (pintype "bidirectional"))
      (node (ref "IC3") (pin "6") (pinfunction "CLR_6") (pintype "input"))
      (node (ref "IC3") (pin "7") (pinfunction "PRE_7") (pintype "input"))
      (node (ref "IC3") (pin "8") (pinfunction "VCC_8") (pintype "bidirectional"))
      (node (ref "IC4") (pin "5") (pinfunction "VCC_5") (pintype "power_in"))
      (node (ref "IC6") (pin "2") (pinfunction "OUT_2") (pintype "passive"))
      (node (ref "R12") (pin "2") (pinfunction "2_2") (pintype "passive"))
      (node (ref "R20") (pin "2") (pinfunction "2_2") (pintype "passive"))
      (node (ref "TP3") (pin "TP") (pinfunction "TP_TP") (pintype "input"))
      (node (ref "X2") (pin "2") (pinfunction "2_2") (pintype "passive"))
    )
    (net (code "52") (name "unconnected-(IC2-PA2-Pad42)") (class "Default")
      (node (ref "IC2") (pin "42") (pinfunction "PA2_42") (pintype "bidirectional"))
    )
    (net (code "53") (name "unconnected-(IC2-PB3-Pad7)") (class "Default")
      (node (ref "IC2") (pin "7") (pinfunction "PB3_7") (pintype "bidirectional"))
    )
    (net (code "54") (name "unconnected-(IC2-PD1-Pad21)") (class "Default")
      (node (ref "IC2") (pin "21") (pinfunction "PD1_21") (pintype "bidirectional"))
    )
    (net (code "55") (name "unconnected-(IC2-PD2-Pad22)") (class "Default")
      (node (ref "IC2") (pin "22") (pinfunction "PD2_22") (pintype "bidirectional"))
    )
    (net (code "56") (name "unconnected-(IC2-PD3-Pad23)") (class "Default")
      (node (ref "IC2") (pin "23") (pinfunction "PD3_23") (pintype "bidirectional"))
    )
    (net (code "57") (name "unconnected-(IC2-PE0-Pad28)") (class "Default")
      (node (ref "IC2") (pin "28") (pinfunction "PE0_28") (pintype "bidirectional"))
    )
    (net (code "58") (name "unconnected-(IC2-PE1-Pad29)") (class "Default")
      (node (ref "IC2") (pin "29") (pinfunction "PE1_29") (pintype "bidirectional"))
    )
    (net (code "59") (name "unconnected-(IC2-PE2-Pad32)") (class "Default")
      (node (ref "IC2") (pin "32") (pinfunction "PE2_32") (pintype "bidirectional"))
    )
    (net (code "60") (name "unconnected-(IC2-PE3-Pad33)") (class "Default")
      (node (ref "IC2") (pin "33") (pinfunction "PE3_33") (pintype "bidirectional"))
    )
    (net (code "61") (name "unconnected-(X1-GND1-PadP$1)") (class "Default")
      (node (ref "X1") (pin "P$1") (pinfunction "GND1_P$1") (pintype "bidirectional"))
    )
    (net (code "62") (name "unconnected-(X1-GND3-PadP$6)") (class "Default")
      (node (ref "X1") (pin "P$6") (pinfunction "GND3_P$6") (pintype "bidirectional"))
    )
    (net (code "63") (name "unconnected-(X1-GND4-PadP$5)") (class "Default")
      (node (ref "X1") (pin "P$5") (pinfunction "GND4_P$5") (pintype "bidirectional"))
    )
    (net (code "64") (name "unconnected-(X1-Pad4)") (class "Default")
      (node (ref "X1") (pin "4") (pinfunction "4_4") (pintype "input"))
    )
    (net (code "65") (name "unconnected-(X3-GND-PadGND1)") (class "Default")
      (node (ref "X3") (pin "GND1") (pinfunction "GND_GND1") (pintype "bidirectional"))
    )
  )
)
